# R122C.net
KiCad netlist of a schematic drawn in EAGLE
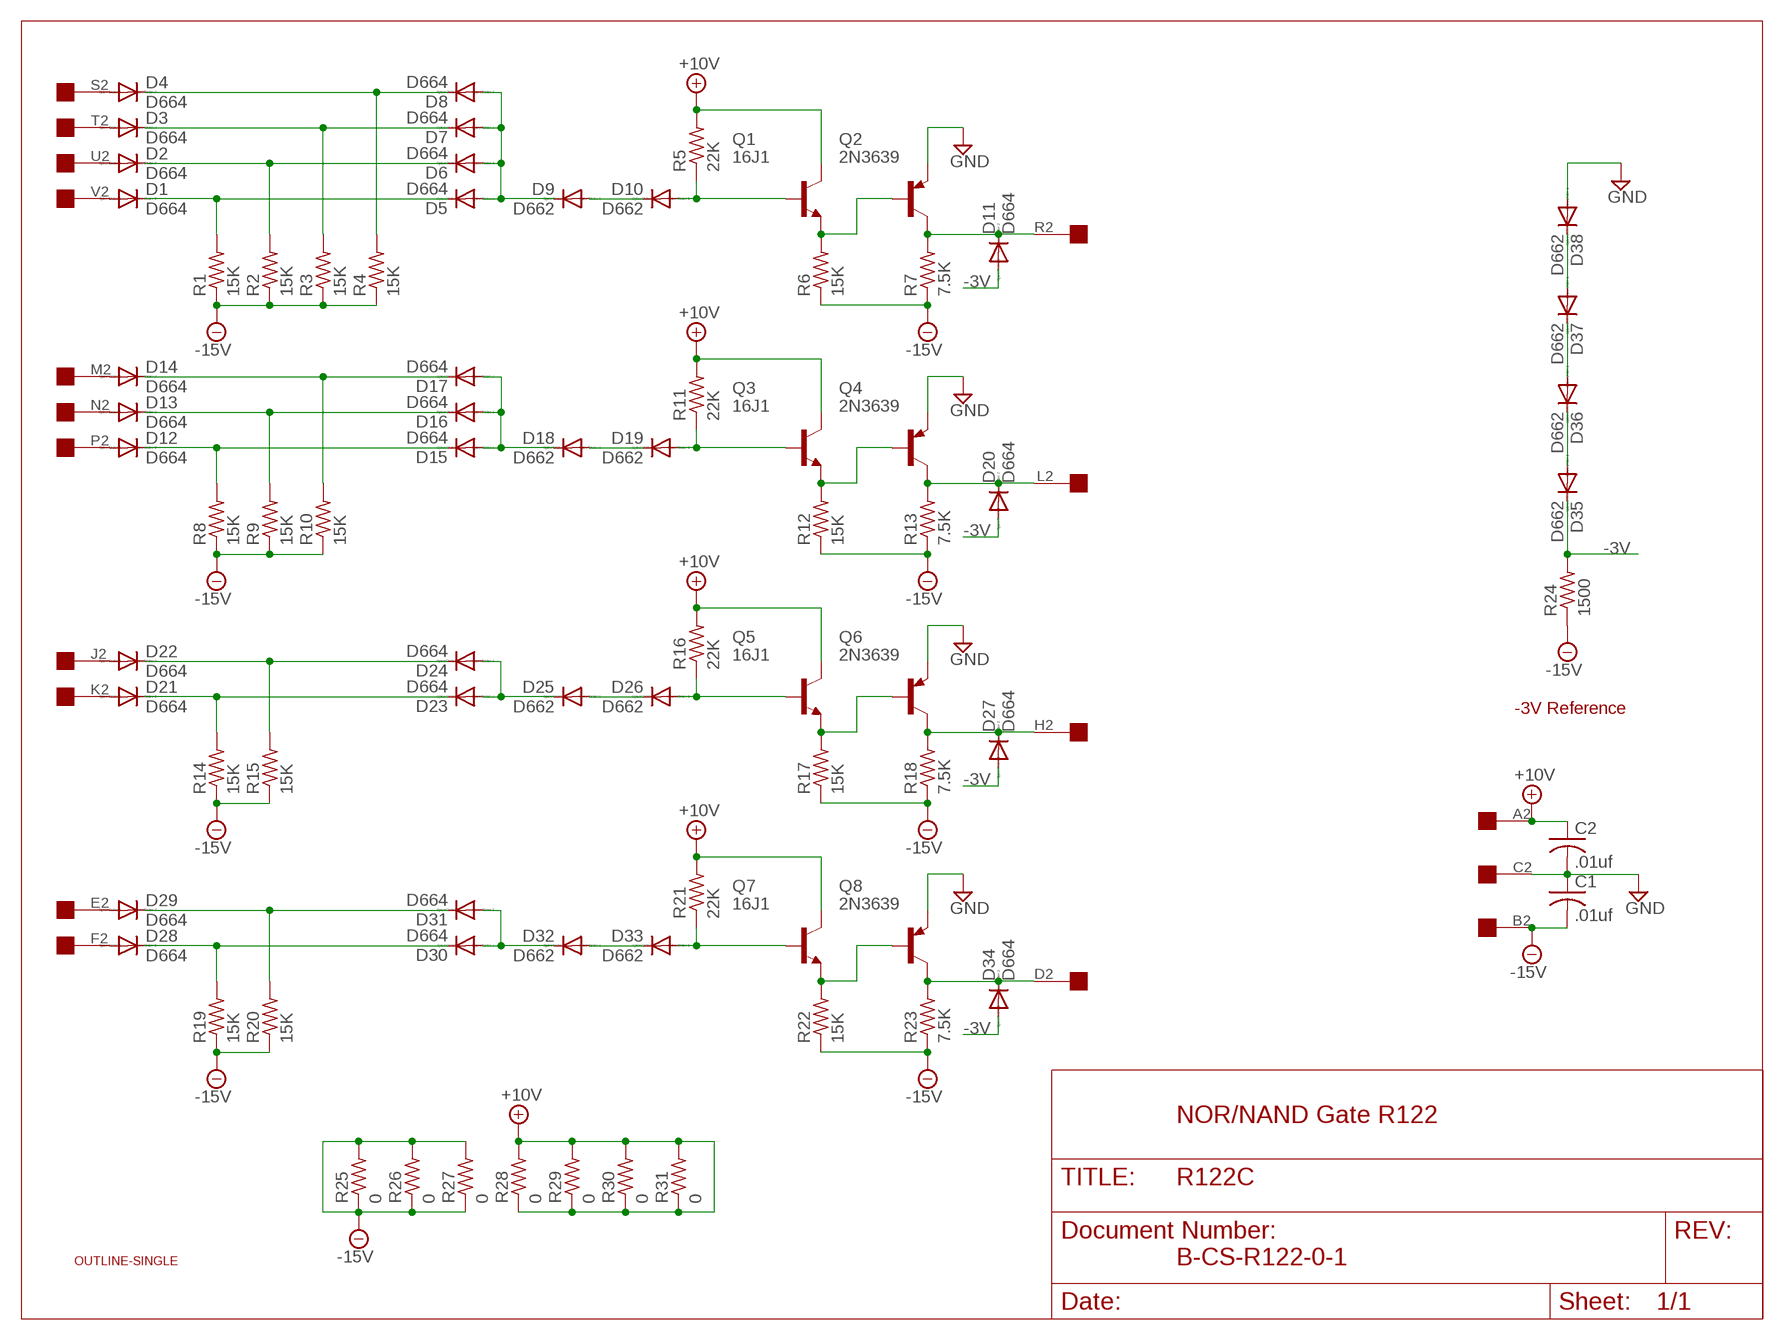
[diagram p0: schematic, sheet 1]

(export (version "E")
  (design (tool "Eeschema 10.0.6"))
  (components
    (comp (ref "C1")
      (value ".01uf")
      (footprint "eagle-import:C063-025X075")
      (libsource (lib "eagle-import") (part "C-US"))
    )
    (comp (ref "C2")
      (value ".01uf")
      (footprint "eagle-import:C063-025X075")
      (libsource (lib "eagle-import") (part "C-US"))
    )
    (comp (ref "D1")
      (value "D664")
      (footprint "eagle-import:DO35-10")
      (libsource (lib "eagle-import") (part "1N4148DO35-10"))
    )
    (comp (ref "D2")
      (value "D664")
      (footprint "eagle-import:DO35-10")
      (libsource (lib "eagle-import") (part "1N4148DO35-10"))
    )
    (comp (ref "D3")
      (value "D664")
      (footprint "eagle-import:DO35-10")
      (libsource (lib "eagle-import") (part "1N4148DO35-10"))
    )
    (comp (ref "D4")
      (value "D664")
      (footprint "eagle-import:DO35-10")
      (libsource (lib "eagle-import") (part "1N4148DO35-10"))
    )
    (comp (ref "D5")
      (value "D664")
      (footprint "eagle-import:DO35-10")
      (libsource (lib "eagle-import") (part "1N4148DO35-10"))
    )
    (comp (ref "D6")
      (value "D664")
      (footprint "eagle-import:DO35-10")
      (libsource (lib "eagle-import") (part "1N4148DO35-10"))
    )
    (comp (ref "D7")
      (value "D664")
      (footprint "eagle-import:DO35-10")
      (libsource (lib "eagle-import") (part "1N4148DO35-10"))
    )
    (comp (ref "D8")
      (value "D664")
      (footprint "eagle-import:DO35-10")
      (libsource (lib "eagle-import") (part "1N4148DO35-10"))
    )
    (comp (ref "D9")
      (value "D662")
      (footprint "eagle-import:DO35-10")
      (libsource (lib "eagle-import") (part "1N4148DO35-10"))
    )
    (comp (ref "D10")
      (value "D662")
      (footprint "eagle-import:DO35-10")
      (libsource (lib "eagle-import") (part "1N4148DO35-10"))
    )
    (comp (ref "D11")
      (value "D664")
      (footprint "eagle-import:DO35-10")
      (libsource (lib "eagle-import") (part "1N4148DO35-10"))
    )
    (comp (ref "D12")
      (value "D664")
      (footprint "eagle-import:DO35-10")
      (libsource (lib "eagle-import") (part "1N4148DO35-10"))
    )
    (comp (ref "D13")
      (value "D664")
      (footprint "eagle-import:DO35-10")
      (libsource (lib "eagle-import") (part "1N4148DO35-10"))
    )
    (comp (ref "D14")
      (value "D664")
      (footprint "eagle-import:DO35-10")
      (libsource (lib "eagle-import") (part "1N4148DO35-10"))
    )
    (comp (ref "D15")
      (value "D664")
      (footprint "eagle-import:DO35-10")
      (libsource (lib "eagle-import") (part "1N4148DO35-10"))
    )
    (comp (ref "D16")
      (value "D664")
      (footprint "eagle-import:DO35-10")
      (libsource (lib "eagle-import") (part "1N4148DO35-10"))
    )
    (comp (ref "D17")
      (value "D664")
      (footprint "eagle-import:DO35-10")
      (libsource (lib "eagle-import") (part "1N4148DO35-10"))
    )
    (comp (ref "D18")
      (value "D662")
      (footprint "eagle-import:DO35-10")
      (libsource (lib "eagle-import") (part "1N4148DO35-10"))
    )
    (comp (ref "D19")
      (value "D662")
      (footprint "eagle-import:DO35-10")
      (libsource (lib "eagle-import") (part "1N4148DO35-10"))
    )
    (comp (ref "D20")
      (value "D664")
      (footprint "eagle-import:DO35-10")
      (libsource (lib "eagle-import") (part "1N4148DO35-10"))
    )
    (comp (ref "D21")
      (value "D664")
      (footprint "eagle-import:DO35-10")
      (libsource (lib "eagle-import") (part "1N4148DO35-10"))
    )
    (comp (ref "D22")
      (value "D664")
      (footprint "eagle-import:DO35-10")
      (libsource (lib "eagle-import") (part "1N4148DO35-10"))
    )
    (comp (ref "D23")
      (value "D664")
      (footprint "eagle-import:DO35-10")
      (libsource (lib "eagle-import") (part "1N4148DO35-10"))
    )
    (comp (ref "D24")
      (value "D664")
      (footprint "eagle-import:DO35-10")
      (libsource (lib "eagle-import") (part "1N4148DO35-10"))
    )
    (comp (ref "D25")
      (value "D662")
      (footprint "eagle-import:DO35-10")
      (libsource (lib "eagle-import") (part "1N4148DO35-10"))
    )
    (comp (ref "D26")
      (value "D662")
      (footprint "eagle-import:DO35-10")
      (libsource (lib "eagle-import") (part "1N4148DO35-10"))
    )
    (comp (ref "D27")
      (value "D664")
      (footprint "eagle-import:DO35-10")
      (libsource (lib "eagle-import") (part "1N4148DO35-10"))
    )
    (comp (ref "D28")
      (value "D664")
      (footprint "eagle-import:DO35-10")
      (libsource (lib "eagle-import") (part "1N4148DO35-10"))
    )
    (comp (ref "D29")
      (value "D664")
      (footprint "eagle-import:DO35-10")
      (libsource (lib "eagle-import") (part "1N4148DO35-10"))
    )
    (comp (ref "D30")
      (value "D664")
      (footprint "eagle-import:DO35-10")
      (libsource (lib "eagle-import") (part "1N4148DO35-10"))
    )
    (comp (ref "D31")
      (value "D664")
      (footprint "eagle-import:DO35-10")
      (libsource (lib "eagle-import") (part "1N4148DO35-10"))
    )
    (comp (ref "D32")
      (value "D662")
      (footprint "eagle-import:DO35-10")
      (libsource (lib "eagle-import") (part "1N4148DO35-10"))
    )
    (comp (ref "D33")
      (value "D662")
      (footprint "eagle-import:DO35-10")
      (libsource (lib "eagle-import") (part "1N4148DO35-10"))
    )
    (comp (ref "D34")
      (value "D664")
      (footprint "eagle-import:DO35-10")
      (libsource (lib "eagle-import") (part "1N4148DO35-10"))
    )
    (comp (ref "D35")
      (value "D662")
      (footprint "eagle-import:DO35-10")
      (libsource (lib "eagle-import") (part "1N4148DO35-10"))
    )
    (comp (ref "D36")
      (value "D662")
      (footprint "eagle-import:DO35-10")
      (libsource (lib "eagle-import") (part "1N4148DO35-10"))
    )
    (comp (ref "D37")
      (value "D662")
      (footprint "eagle-import:DO35-10")
      (libsource (lib "eagle-import") (part "1N4148DO35-10"))
    )
    (comp (ref "D38")
      (value "D662")
      (footprint "eagle-import:DO35-10")
      (libsource (lib "eagle-import") (part "1N4148DO35-10"))
    )
    (comp (ref "Q1")
      (value "16J1")
      (footprint "eagle-import:TO39")
      (libsource (lib "eagle-import") (part "-NPN-TO39-EBC2N1711"))
    )
    (comp (ref "Q2")
      (value "2N3639")
      (footprint "eagle-import:TO39")
      (libsource (lib "eagle-import") (part "2N3637"))
    )
    (comp (ref "Q3")
      (value "16J1")
      (footprint "eagle-import:TO39")
      (libsource (lib "eagle-import") (part "-NPN-TO39-EBC2N1711"))
    )
    (comp (ref "Q4")
      (value "2N3639")
      (footprint "eagle-import:TO39")
      (libsource (lib "eagle-import") (part "2N3637"))
    )
    (comp (ref "Q5")
      (value "16J1")
      (footprint "eagle-import:TO39")
      (libsource (lib "eagle-import") (part "-NPN-TO39-EBC2N1711"))
    )
    (comp (ref "Q6")
      (value "2N3639")
      (footprint "eagle-import:TO39")
      (libsource (lib "eagle-import") (part "2N3637"))
    )
    (comp (ref "Q7")
      (value "16J1")
      (footprint "eagle-import:TO39")
      (libsource (lib "eagle-import") (part "-NPN-TO39-EBC2N1711"))
    )
    (comp (ref "Q8")
      (value "2N3639")
      (footprint "eagle-import:TO39")
      (libsource (lib "eagle-import") (part "2N3637"))
    )
    (comp (ref "R1")
      (value "15K")
      (footprint "eagle-import:0207_10")
      (libsource (lib "eagle-import") (part "R-US_0207/10"))
    )
    (comp (ref "R2")
      (value "15K")
      (footprint "eagle-import:0207_10")
      (libsource (lib "eagle-import") (part "R-US_0207/10"))
    )
    (comp (ref "R3")
      (value "15K")
      (footprint "eagle-import:0207_10")
      (libsource (lib "eagle-import") (part "R-US_0207/10"))
    )
    (comp (ref "R4")
      (value "15K")
      (footprint "eagle-import:0207_10")
      (libsource (lib "eagle-import") (part "R-US_0207/10"))
    )
    (comp (ref "R5")
      (value "22K")
      (footprint "eagle-import:0207_10")
      (libsource (lib "eagle-import") (part "R-US_0207/10"))
    )
    (comp (ref "R6")
      (value "15K")
      (footprint "eagle-import:0207_10")
      (libsource (lib "eagle-import") (part "R-US_0207/10"))
    )
    (comp (ref "R7")
      (value "7.5K")
      (footprint "eagle-import:0207_10")
      (libsource (lib "eagle-import") (part "R-US_0207/10"))
    )
    (comp (ref "R8")
      (value "15K")
      (footprint "eagle-import:0207_10")
      (libsource (lib "eagle-import") (part "R-US_0207/10"))
    )
    (comp (ref "R9")
      (value "15K")
      (footprint "eagle-import:0207_10")
      (libsource (lib "eagle-import") (part "R-US_0207/10"))
    )
    (comp (ref "R10")
      (value "15K")
      (footprint "eagle-import:0207_10")
      (libsource (lib "eagle-import") (part "R-US_0207/10"))
    )
    (comp (ref "R11")
      (value "22K")
      (footprint "eagle-import:0207_10")
      (libsource (lib "eagle-import") (part "R-US_0207/10"))
    )
    (comp (ref "R12")
      (value "15K")
      (footprint "eagle-import:0207_10")
      (libsource (lib "eagle-import") (part "R-US_0207/10"))
    )
    (comp (ref "R13")
      (value "7.5K")
      (footprint "eagle-import:0207_10")
      (libsource (lib "eagle-import") (part "R-US_0207/10"))
    )
    (comp (ref "R14")
      (value "15K")
      (footprint "eagle-import:0207_10")
      (libsource (lib "eagle-import") (part "R-US_0207/10"))
    )
    (comp (ref "R15")
      (value "15K")
      (footprint "eagle-import:0207_10")
      (libsource (lib "eagle-import") (part "R-US_0207/10"))
    )
    (comp (ref "R16")
      (value "22K")
      (footprint "eagle-import:0207_10")
      (libsource (lib "eagle-import") (part "R-US_0207/10"))
    )
    (comp (ref "R17")
      (value "15K")
      (footprint "eagle-import:0207_10")
      (libsource (lib "eagle-import") (part "R-US_0207/10"))
    )
    (comp (ref "R18")
      (value "7.5K")
      (footprint "eagle-import:0207_10")
      (libsource (lib "eagle-import") (part "R-US_0207/10"))
    )
    (comp (ref "R19")
      (value "15K")
      (footprint "eagle-import:0207_10")
      (libsource (lib "eagle-import") (part "R-US_0207/10"))
    )
    (comp (ref "R20")
      (value "15K")
      (footprint "eagle-import:0207_10")
      (libsource (lib "eagle-import") (part "R-US_0207/10"))
    )
    (comp (ref "R21")
      (value "22K")
      (footprint "eagle-import:0207_10")
      (libsource (lib "eagle-import") (part "R-US_0207/10"))
    )
    (comp (ref "R22")
      (value "15K")
      (footprint "eagle-import:0207_10")
      (libsource (lib "eagle-import") (part "R-US_0207/10"))
    )
    (comp (ref "R23")
      (value "7.5K")
      (footprint "eagle-import:0207_10")
      (libsource (lib "eagle-import") (part "R-US_0207/10"))
    )
    (comp (ref "R24")
      (value "1500")
      (footprint "eagle-import:0207_10")
      (libsource (lib "eagle-import") (part "R-US_0207/10"))
    )
    (comp (ref "R25")
      (value "0")
      (footprint "eagle-import:0207_10")
      (libsource (lib "eagle-import") (part "R-US_0207/10"))
    )
    (comp (ref "R26")
      (value "0")
      (footprint "eagle-import:0207_10")
      (libsource (lib "eagle-import") (part "R-US_0207/10"))
    )
    (comp (ref "R27")
      (value "0")
      (footprint "eagle-import:0207_10")
      (libsource (lib "eagle-import") (part "R-US_0207/10"))
    )
    (comp (ref "R28")
      (value "0")
      (footprint "eagle-import:0207_10")
      (libsource (lib "eagle-import") (part "R-US_0207/10"))
    )
    (comp (ref "R29")
      (value "0")
      (footprint "eagle-import:0207_10")
      (libsource (lib "eagle-import") (part "R-US_0207/10"))
    )
    (comp (ref "R30")
      (value "0")
      (footprint "eagle-import:0207_10")
      (libsource (lib "eagle-import") (part "R-US_0207/10"))
    )
    (comp (ref "R31")
      (value "0")
      (footprint "eagle-import:0207_10")
      (libsource (lib "eagle-import") (part "R-US_0207/10"))
    )
    (comp (ref "U$1")
      (value "OUTLINE-SINGLE")
      (footprint "eagle-import:SINGLE")
      (libsource (lib "eagle-import") (part "OUTLINE-SINGLE"))
    )
    (comp (ref "U$2")
      (value "EDGE-1")
      (footprint "eagle-import:EDGE-CON1")
      (libsource (lib "eagle-import") (part "EDGE-1"))
    )
  )
  (nets
    (net (code "1") (name "+10V") (class "Default")
      (node (ref "C2") (pin "1") (pinfunction "1_1") (pintype "passive"))
      (node (ref "Q1") (pin "3") (pinfunction "C_3") (pintype "passive"))
      (node (ref "Q3") (pin "3") (pinfunction "C_3") (pintype "passive"))
      (node (ref "Q5") (pin "3") (pinfunction "C_3") (pintype "passive"))
      (node (ref "Q7") (pin "3") (pinfunction "C_3") (pintype "passive"))
      (node (ref "R11") (pin "2") (pinfunction "2_2") (pintype "passive"))
      (node (ref "R16") (pin "2") (pinfunction "2_2") (pintype "passive"))
      (node (ref "R21") (pin "2") (pinfunction "2_2") (pintype "passive"))
      (node (ref "R28") (pin "1") (pinfunction "1_1") (pintype "passive"))
      (node (ref "R28") (pin "2") (pinfunction "2_2") (pintype "passive"))
      (node (ref "R29") (pin "1") (pinfunction "1_1") (pintype "passive"))
      (node (ref "R29") (pin "2") (pinfunction "2_2") (pintype "passive"))
      (node (ref "R30") (pin "1") (pinfunction "1_1") (pintype "passive"))
      (node (ref "R30") (pin "2") (pinfunction "2_2") (pintype "passive"))
      (node (ref "R31") (pin "1") (pinfunction "1_1") (pintype "passive"))
      (node (ref "R31") (pin "2") (pinfunction "2_2") (pintype "passive"))
      (node (ref "R5") (pin "2") (pinfunction "2_2") (pintype "passive"))
      (node (ref "U$2") (pin "A2") (pinfunction "1_A2") (pintype "bidirectional"))
    )
    (net (code "2") (name "-15V") (class "Default")
      (node (ref "C1") (pin "2") (pinfunction "2_2") (pintype "passive"))
      (node (ref "R1") (pin "1") (pinfunction "1_1") (pintype "passive"))
      (node (ref "R10") (pin "1") (pinfunction "1_1") (pintype "passive"))
      (node (ref "R12") (pin "1") (pinfunction "1_1") (pintype "passive"))
      (node (ref "R13") (pin "1") (pinfunction "1_1") (pintype "passive"))
      (node (ref "R14") (pin "1") (pinfunction "1_1") (pintype "passive"))
      (node (ref "R15") (pin "1") (pinfunction "1_1") (pintype "passive"))
      (node (ref "R17") (pin "1") (pinfunction "1_1") (pintype "passive"))
      (node (ref "R18") (pin "1") (pinfunction "1_1") (pintype "passive"))
      (node (ref "R19") (pin "1") (pinfunction "1_1") (pintype "passive"))
      (node (ref "R2") (pin "1") (pinfunction "1_1") (pintype "passive"))
      (node (ref "R20") (pin "1") (pinfunction "1_1") (pintype "passive"))
      (node (ref "R22") (pin "1") (pinfunction "1_1") (pintype "passive"))
      (node (ref "R23") (pin "1") (pinfunction "1_1") (pintype "passive"))
      (node (ref "R24") (pin "1") (pinfunction "1_1") (pintype "passive"))
      (node (ref "R25") (pin "1") (pinfunction "1_1") (pintype "passive"))
      (node (ref "R25") (pin "2") (pinfunction "2_2") (pintype "passive"))
      (node (ref "R26") (pin "1") (pinfunction "1_1") (pintype "passive"))
      (node (ref "R26") (pin "2") (pinfunction "2_2") (pintype "passive"))
      (node (ref "R27") (pin "1") (pinfunction "1_1") (pintype "passive"))
      (node (ref "R27") (pin "2") (pinfunction "2_2") (pintype "passive"))
      (node (ref "R3") (pin "1") (pinfunction "1_1") (pintype "passive"))
      (node (ref "R4") (pin "1") (pinfunction "1_1") (pintype "passive"))
      (node (ref "R6") (pin "1") (pinfunction "1_1") (pintype "passive"))
      (node (ref "R7") (pin "1") (pinfunction "1_1") (pintype "passive"))
      (node (ref "R8") (pin "1") (pinfunction "1_1") (pintype "passive"))
      (node (ref "R9") (pin "1") (pinfunction "1_1") (pintype "passive"))
      (node (ref "U$2") (pin "B2") (pinfunction "1_B2") (pintype "bidirectional"))
    )
    (net (code "3") (name "/-3V") (class "Default")
      (node (ref "D11") (pin "A") (pinfunction "A_A") (pintype "passive"))
      (node (ref "D20") (pin "A") (pinfunction "A_A") (pintype "passive"))
      (node (ref "D27") (pin "A") (pinfunction "A_A") (pintype "passive"))
      (node (ref "D34") (pin "A") (pinfunction "A_A") (pintype "passive"))
      (node (ref "D35") (pin "C") (pinfunction "C_C") (pintype "passive"))
      (node (ref "R24") (pin "2") (pinfunction "2_2") (pintype "passive"))
    )
    (net (code "4") (name "GND") (class "Default")
      (node (ref "C1") (pin "1") (pinfunction "1_1") (pintype "passive"))
      (node (ref "C2") (pin "2") (pinfunction "2_2") (pintype "passive"))
      (node (ref "D38") (pin "A") (pinfunction "A_A") (pintype "passive"))
      (node (ref "Q2") (pin "1") (pinfunction "E_1") (pintype "passive"))
      (node (ref "Q4") (pin "1") (pinfunction "E_1") (pintype "passive"))
      (node (ref "Q6") (pin "1") (pinfunction "E_1") (pintype "passive"))
      (node (ref "Q8") (pin "1") (pinfunction "E_1") (pintype "passive"))
      (node (ref "U$2") (pin "C2") (pinfunction "1_C2") (pintype "bidirectional"))
    )
    (net (code "5") (name "Net-(D1-PadC)") (class "Default")
      (node (ref "D1") (pin "C") (pinfunction "C_C") (pintype "passive"))
      (node (ref "D5") (pin "C") (pinfunction "C_C") (pintype "passive"))
      (node (ref "R1") (pin "2") (pinfunction "2_2") (pintype "passive"))
    )
    (net (code "6") (name "Net-(D2-PadC)") (class "Default")
      (node (ref "D2") (pin "C") (pinfunction "C_C") (pintype "passive"))
      (node (ref "D6") (pin "C") (pinfunction "C_C") (pintype "passive"))
      (node (ref "R2") (pin "2") (pinfunction "2_2") (pintype "passive"))
    )
    (net (code "7") (name "Net-(D3-PadC)") (class "Default")
      (node (ref "D3") (pin "C") (pinfunction "C_C") (pintype "passive"))
      (node (ref "D7") (pin "C") (pinfunction "C_C") (pintype "passive"))
      (node (ref "R3") (pin "2") (pinfunction "2_2") (pintype "passive"))
    )
    (net (code "8") (name "Net-(D4-PadC)") (class "Default")
      (node (ref "D4") (pin "C") (pinfunction "C_C") (pintype "passive"))
      (node (ref "D8") (pin "C") (pinfunction "C_C") (pintype "passive"))
      (node (ref "R4") (pin "2") (pinfunction "2_2") (pintype "passive"))
    )
    (net (code "9") (name "Net-(D5-PadA)") (class "Default")
      (node (ref "D5") (pin "A") (pinfunction "A_A") (pintype "passive"))
      (node (ref "D6") (pin "A") (pinfunction "A_A") (pintype "passive"))
      (node (ref "D7") (pin "A") (pinfunction "A_A") (pintype "passive"))
      (node (ref "D8") (pin "A") (pinfunction "A_A") (pintype "passive"))
      (node (ref "D9") (pin "C") (pinfunction "C_C") (pintype "passive"))
    )
    (net (code "10") (name "Net-(D10-PadC)") (class "Default")
      (node (ref "D10") (pin "C") (pinfunction "C_C") (pintype "passive"))
      (node (ref "D9") (pin "A") (pinfunction "A_A") (pintype "passive"))
    )
    (net (code "11") (name "Net-(D12-PadC)") (class "Default")
      (node (ref "D12") (pin "C") (pinfunction "C_C") (pintype "passive"))
      (node (ref "D15") (pin "C") (pinfunction "C_C") (pintype "passive"))
      (node (ref "R8") (pin "2") (pinfunction "2_2") (pintype "passive"))
    )
    (net (code "12") (name "Net-(D13-PadC)") (class "Default")
      (node (ref "D13") (pin "C") (pinfunction "C_C") (pintype "passive"))
      (node (ref "D16") (pin "C") (pinfunction "C_C") (pintype "passive"))
      (node (ref "R9") (pin "2") (pinfunction "2_2") (pintype "passive"))
    )
    (net (code "13") (name "Net-(D14-PadC)") (class "Default")
      (node (ref "D14") (pin "C") (pinfunction "C_C") (pintype "passive"))
      (node (ref "D17") (pin "C") (pinfunction "C_C") (pintype "passive"))
      (node (ref "R10") (pin "2") (pinfunction "2_2") (pintype "passive"))
    )
    (net (code "14") (name "Net-(D15-PadA)") (class "Default")
      (node (ref "D15") (pin "A") (pinfunction "A_A") (pintype "passive"))
      (node (ref "D16") (pin "A") (pinfunction "A_A") (pintype "passive"))
      (node (ref "D17") (pin "A") (pinfunction "A_A") (pintype "passive"))
      (node (ref "D18") (pin "C") (pinfunction "C_C") (pintype "passive"))
    )
    (net (code "15") (name "Net-(D18-PadA)") (class "Default")
      (node (ref "D18") (pin "A") (pinfunction "A_A") (pintype "passive"))
      (node (ref "D19") (pin "C") (pinfunction "C_C") (pintype "passive"))
    )
    (net (code "16") (name "Net-(D21-PadC)") (class "Default")
      (node (ref "D21") (pin "C") (pinfunction "C_C") (pintype "passive"))
      (node (ref "D23") (pin "C") (pinfunction "C_C") (pintype "passive"))
      (node (ref "R14") (pin "2") (pinfunction "2_2") (pintype "passive"))
    )
    (net (code "17") (name "Net-(D22-PadC)") (class "Default")
      (node (ref "D22") (pin "C") (pinfunction "C_C") (pintype "passive"))
      (node (ref "D24") (pin "C") (pinfunction "C_C") (pintype "passive"))
      (node (ref "R15") (pin "2") (pinfunction "2_2") (pintype "passive"))
    )
    (net (code "18") (name "Net-(D23-PadA)") (class "Default")
      (node (ref "D23") (pin "A") (pinfunction "A_A") (pintype "passive"))
      (node (ref "D24") (pin "A") (pinfunction "A_A") (pintype "passive"))
      (node (ref "D25") (pin "C") (pinfunction "C_C") (pintype "passive"))
    )
    (net (code "19") (name "Net-(D25-PadA)") (class "Default")
      (node (ref "D25") (pin "A") (pinfunction "A_A") (pintype "passive"))
      (node (ref "D26") (pin "C") (pinfunction "C_C") (pintype "passive"))
    )
    (net (code "20") (name "Net-(D28-PadC)") (class "Default")
      (node (ref "D28") (pin "C") (pinfunction "C_C") (pintype "passive"))
      (node (ref "D30") (pin "C") (pinfunction "C_C") (pintype "passive"))
      (node (ref "R19") (pin "2") (pinfunction "2_2") (pintype "passive"))
    )
    (net (code "21") (name "Net-(D29-PadC)") (class "Default")
      (node (ref "D29") (pin "C") (pinfunction "C_C") (pintype "passive"))
      (node (ref "D31") (pin "C") (pinfunction "C_C") (pintype "passive"))
      (node (ref "R20") (pin "2") (pinfunction "2_2") (pintype "passive"))
    )
    (net (code "22") (name "Net-(D30-PadA)") (class "Default")
      (node (ref "D30") (pin "A") (pinfunction "A_A") (pintype "passive"))
      (node (ref "D31") (pin "A") (pinfunction "A_A") (pintype "passive"))
      (node (ref "D32") (pin "C") (pinfunction "C_C") (pintype "passive"))
    )
    (net (code "23") (name "Net-(D32-PadA)") (class "Default")
      (node (ref "D32") (pin "A") (pinfunction "A_A") (pintype "passive"))
      (node (ref "D33") (pin "C") (pinfunction "C_C") (pintype "passive"))
    )
    (net (code "24") (name "Net-(D35-PadA)") (class "Default")
      (node (ref "D35") (pin "A") (pinfunction "A_A") (pintype "passive"))
      (node (ref "D36") (pin "C") (pinfunction "C_C") (pintype "passive"))
    )
    (net (code "25") (name "Net-(D36-PadA)") (class "Default")
      (node (ref "D36") (pin "A") (pinfunction "A_A") (pintype "passive"))
      (node (ref "D37") (pin "C") (pinfunction "C_C") (pintype "passive"))
    )
    (net (code "26") (name "Net-(D37-PadA)") (class "Default")
      (node (ref "D37") (pin "A") (pinfunction "A_A") (pintype "passive"))
      (node (ref "D38") (pin "C") (pinfunction "C_C") (pintype "passive"))
    )
    (net (code "27") (name "Net-(Q1-B)") (class "Default")
      (node (ref "D10") (pin "A") (pinfunction "A_A") (pintype "passive"))
      (node (ref "Q1") (pin "2") (pinfunction "B_2") (pintype "passive"))
      (node (ref "R5") (pin "1") (pinfunction "1_1") (pintype "passive"))
    )
    (net (code "28") (name "Net-(Q1-E)") (class "Default")
      (node (ref "Q1") (pin "1") (pinfunction "E_1") (pintype "passive"))
      (node (ref "Q2") (pin "2") (pinfunction "B_2") (pintype "passive"))
      (node (ref "R6") (pin "2") (pinfunction "2_2") (pintype "passive"))
    )
    (net (code "29") (name "Net-(Q2-C)") (class "Default")
      (node (ref "D11") (pin "C") (pinfunction "C_C") (pintype "passive"))
      (node (ref "Q2") (pin "3") (pinfunction "C_3") (pintype "passive"))
      (node (ref "R7") (pin "2") (pinfunction "2_2") (pintype "passive"))
      (node (ref "U$2") (pin "R2") (pinfunction "1_R2") (pintype "bidirectional"))
    )
    (net (code "30") (name "Net-(Q3-B)") (class "Default")
      (node (ref "D19") (pin "A") (pinfunction "A_A") (pintype "passive"))
      (node (ref "Q3") (pin "2") (pinfunction "B_2") (pintype "passive"))
      (node (ref "R11") (pin "1") (pinfunction "1_1") (pintype "passive"))
    )
    (net (code "31") (name "Net-(Q3-E)") (class "Default")
      (node (ref "Q3") (pin "1") (pinfunction "E_1") (pintype "passive"))
      (node (ref "Q4") (pin "2") (pinfunction "B_2") (pintype "passive"))
      (node (ref "R12") (pin "2") (pinfunction "2_2") (pintype "passive"))
    )
    (net (code "32") (name "Net-(Q4-C)") (class "Default")
      (node (ref "D20") (pin "C") (pinfunction "C_C") (pintype "passive"))
      (node (ref "Q4") (pin "3") (pinfunction "C_3") (pintype "passive"))
      (node (ref "R13") (pin "2") (pinfunction "2_2") (pintype "passive"))
      (node (ref "U$2") (pin "L2") (pinfunction "1_L2") (pintype "bidirectional"))
    )
    (net (code "33") (name "Net-(Q5-B)") (class "Default")
      (node (ref "D26") (pin "A") (pinfunction "A_A") (pintype "passive"))
      (node (ref "Q5") (pin "2") (pinfunction "B_2") (pintype "passive"))
      (node (ref "R16") (pin "1") (pinfunction "1_1") (pintype "passive"))
    )
    (net (code "34") (name "Net-(Q5-E)") (class "Default")
      (node (ref "Q5") (pin "1") (pinfunction "E_1") (pintype "passive"))
      (node (ref "Q6") (pin "2") (pinfunction "B_2") (pintype "passive"))
      (node (ref "R17") (pin "2") (pinfunction "2_2") (pintype "passive"))
    )
    (net (code "35") (name "Net-(Q6-C)") (class "Default")
      (node (ref "D27") (pin "C") (pinfunction "C_C") (pintype "passive"))
      (node (ref "Q6") (pin "3") (pinfunction "C_3") (pintype "passive"))
      (node (ref "R18") (pin "2") (pinfunction "2_2") (pintype "passive"))
      (node (ref "U$2") (pin "H2") (pinfunction "1_H2") (pintype "bidirectional"))
    )
    (net (code "36") (name "Net-(Q7-B)") (class "Default")
      (node (ref "D33") (pin "A") (pinfunction "A_A") (pintype "passive"))
      (node (ref "Q7") (pin "2") (pinfunction "B_2") (pintype "passive"))
      (node (ref "R21") (pin "1") (pinfunction "1_1") (pintype "passive"))
    )
    (net (code "37") (name "Net-(Q7-E)") (class "Default")
      (node (ref "Q7") (pin "1") (pinfunction "E_1") (pintype "passive"))
      (node (ref "Q8") (pin "2") (pinfunction "B_2") (pintype "passive"))
      (node (ref "R22") (pin "2") (pinfunction "2_2") (pintype "passive"))
    )
    (net (code "38") (name "Net-(Q8-C)") (class "Default")
      (node (ref "D34") (pin "C") (pinfunction "C_C") (pintype "passive"))
      (node (ref "Q8") (pin "3") (pinfunction "C_3") (pintype "passive"))
      (node (ref "R23") (pin "2") (pinfunction "2_2") (pintype "passive"))
      (node (ref "U$2") (pin "D2") (pinfunction "1_D2") (pintype "bidirectional"))
    )
    (net (code "39") (name "Net-(U$2E-1)") (class "Default")
      (node (ref "D29") (pin "A") (pinfunction "A_A") (pintype "passive"))
      (node (ref "U$2") (pin "E2") (pinfunction "1_E2") (pintype "bidirectional"))
    )
    (net (code "40") (name "Net-(U$2F-1)") (class "Default")
      (node (ref "D28") (pin "A") (pinfunction "A_A") (pintype "passive"))
      (node (ref "U$2") (pin "F2") (pinfunction "1_F2") (pintype "bidirectional"))
    )
    (net (code "41") (name "Net-(U$2H-1)") (class "Default")
      (node (ref "D22") (pin "A") (pinfunction "A_A") (pintype "passive"))
      (node (ref "U$2") (pin "J2") (pinfunction "1_J2") (pintype "bidirectional"))
    )
    (net (code "42") (name "Net-(U$2I-1)") (class "Default")
      (node (ref "D21") (pin "A") (pinfunction "A_A") (pintype "passive"))
      (node (ref "U$2") (pin "K2") (pinfunction "1_K2") (pintype "bidirectional"))
    )
    (net (code "43") (name "Net-(U$2K-1)") (class "Default")
      (node (ref "D14") (pin "A") (pinfunction "A_A") (pintype "passive"))
      (node (ref "U$2") (pin "M2") (pinfunction "1_M2") (pintype "bidirectional"))
    )
    (net (code "44") (name "Net-(U$2L-1)") (class "Default")
      (node (ref "D13") (pin "A") (pinfunction "A_A") (pintype "passive"))
      (node (ref "U$2") (pin "N2") (pinfunction "1_N2") (pintype "bidirectional"))
    )
    (net (code "45") (name "Net-(U$2M-1)") (class "Default")
      (node (ref "D12") (pin "A") (pinfunction "A_A") (pintype "passive"))
      (node (ref "U$2") (pin "P2") (pinfunction "1_P2") (pintype "bidirectional"))
    )
    (net (code "46") (name "Net-(U$2O-1)") (class "Default")
      (node (ref "D4") (pin "A") (pinfunction "A_A") (pintype "passive"))
      (node (ref "U$2") (pin "S2") (pinfunction "1_S2") (pintype "bidirectional"))
    )
    (net (code "47") (name "Net-(U$2P-1)") (class "Default")
      (node (ref "D3") (pin "A") (pinfunction "A_A") (pintype "passive"))
      (node (ref "U$2") (pin "T2") (pinfunction "1_T2") (pintype "bidirectional"))
    )
    (net (code "48") (name "Net-(U$2Q-1)") (class "Default")
      (node (ref "D2") (pin "A") (pinfunction "A_A") (pintype "passive"))
      (node (ref "U$2") (pin "U2") (pinfunction "1_U2") (pintype "bidirectional"))
    )
    (net (code "49") (name "Net-(U$2R-1)") (class "Default")
      (node (ref "D1") (pin "A") (pinfunction "A_A") (pintype "passive"))
      (node (ref "U$2") (pin "V2") (pinfunction "1_V2") (pintype "bidirectional"))
    )
  )
)
